# trailGuard.net
KiCad netlist of a schematic drawn in Altium Designer
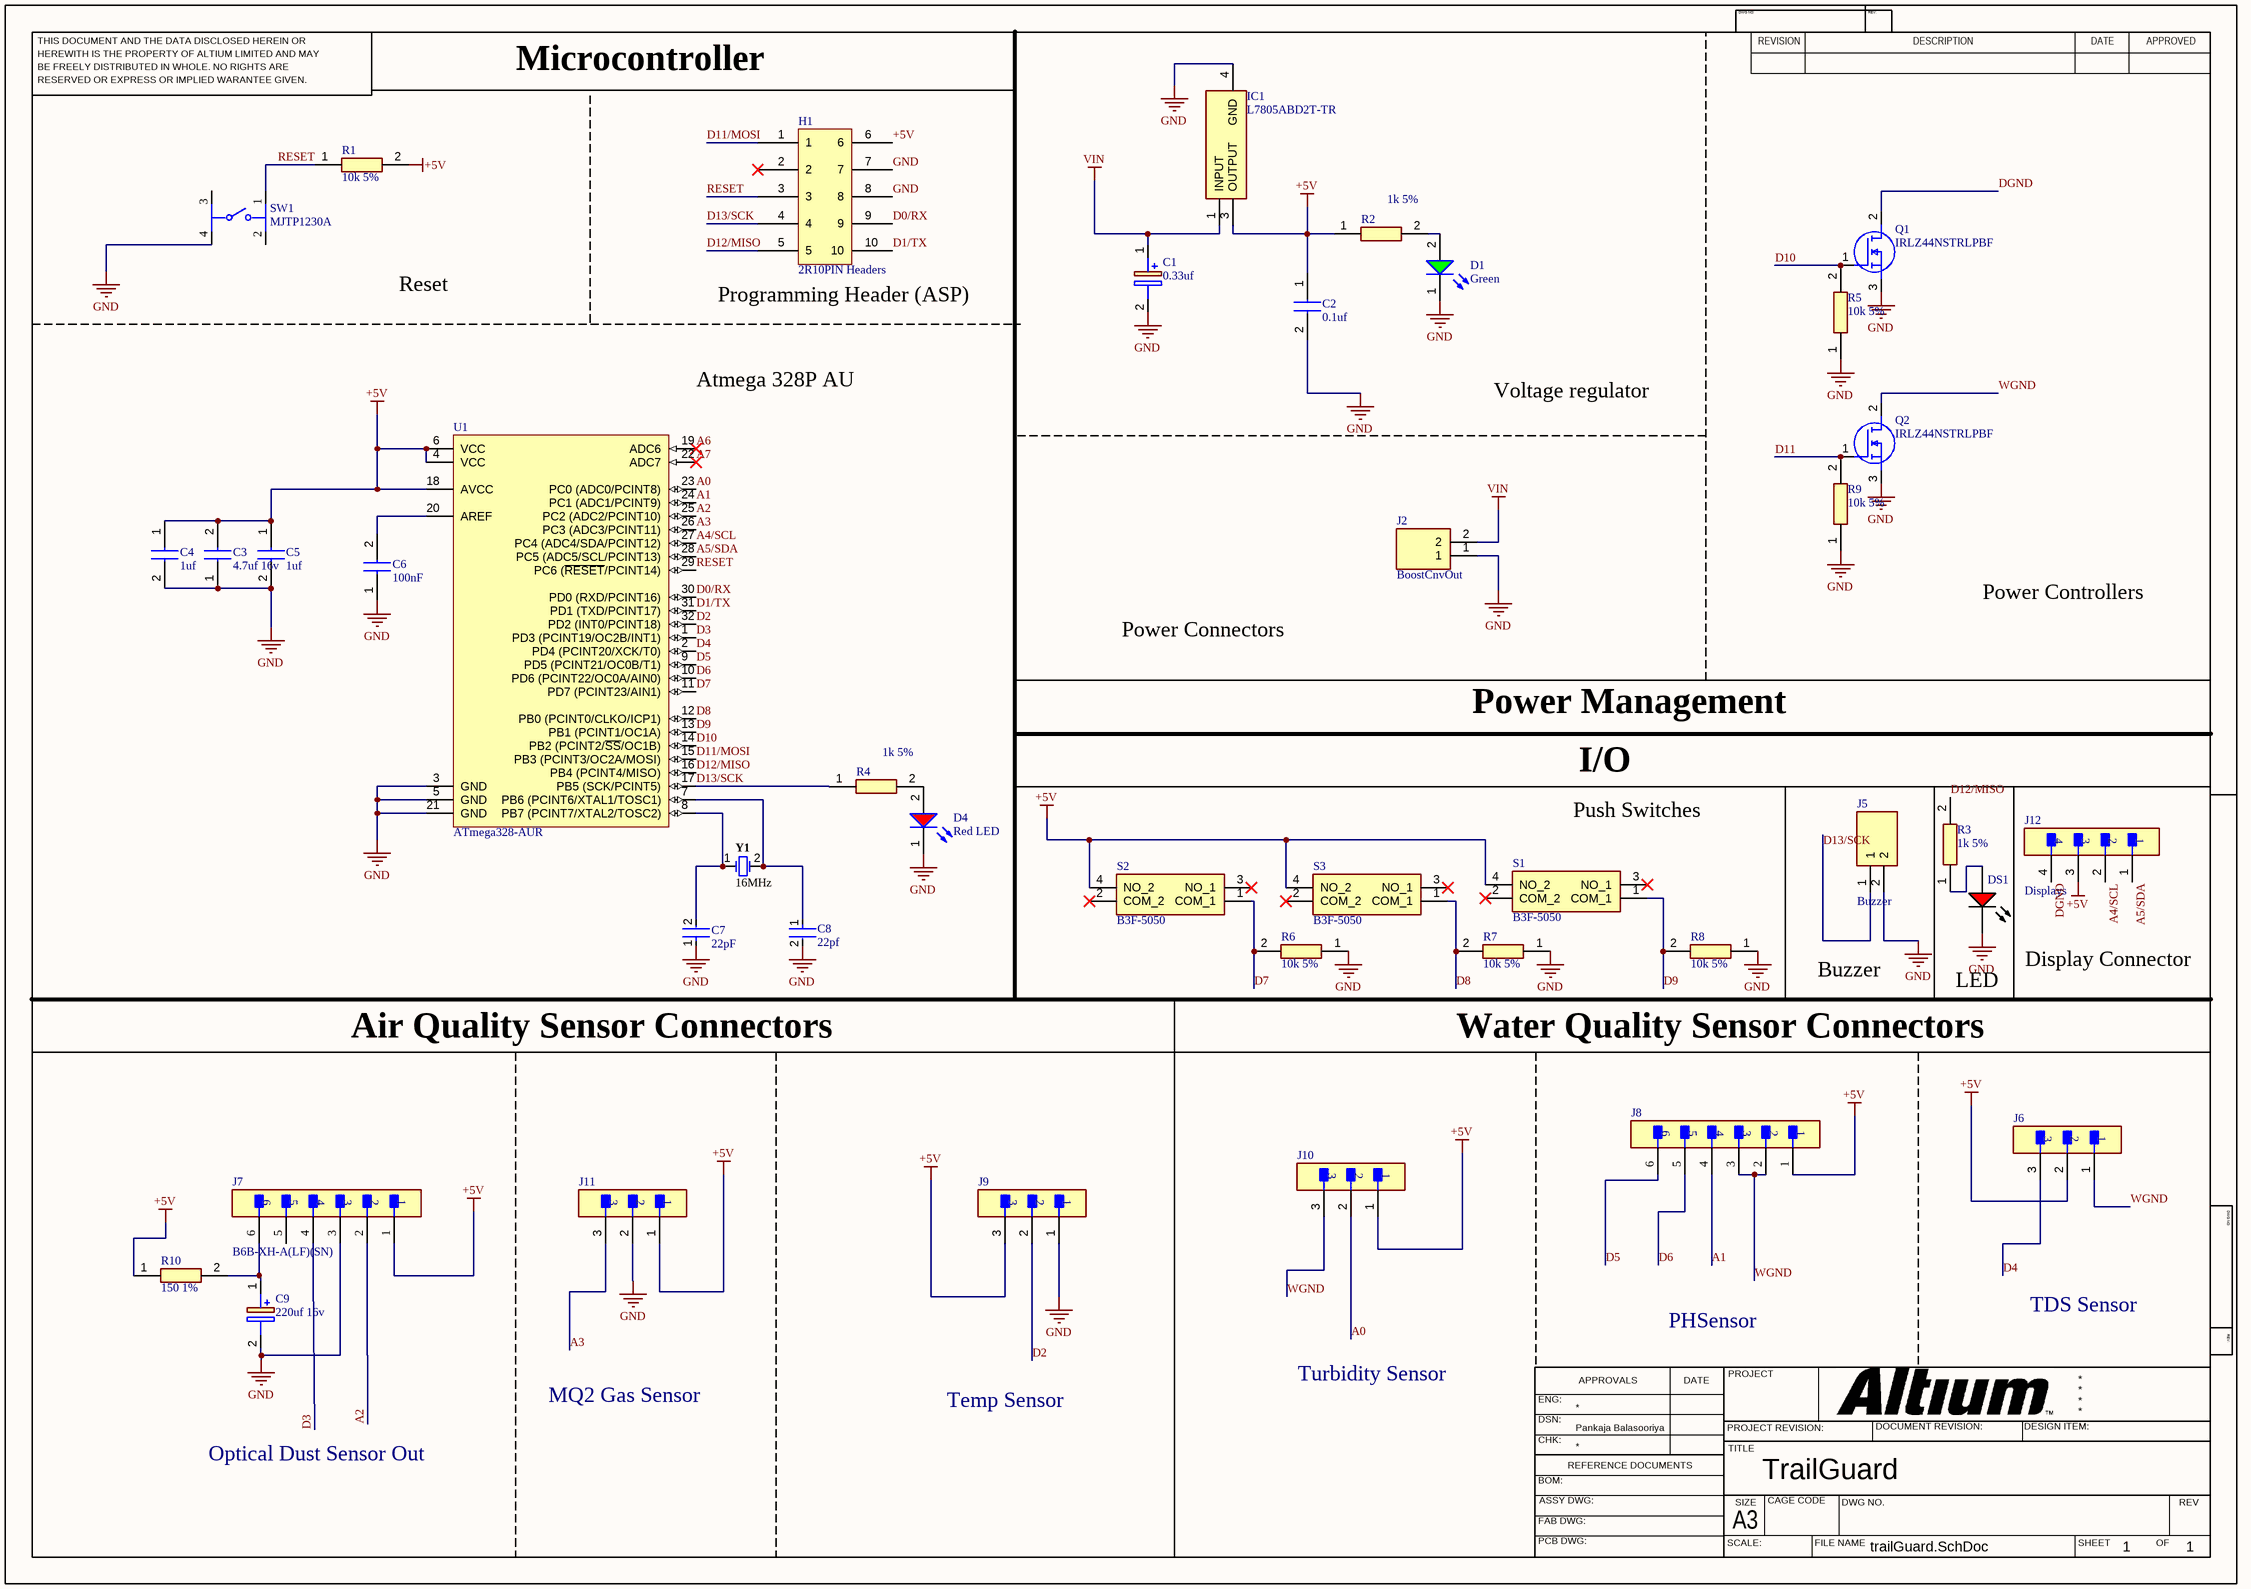
[diagram p0: trailGuard.SchDoc]

(export (version "E")
  (design (tool "Eeschema 10.0.6"))
  (components
    (comp (ref "C1")
      (value "0.33uf")
      (footprint "SamacSys:CAPPM3216X180N")
      (description "Capacitor Polarised")
      (fields
        (field (name "MANUFACTURER_PART_NUMBER") "293D334X9035A2TE3")
        (field (name "MOUSER PART NUMBER") "74-293D334X9035A2TE3")
      )
      (libsource (lib "*") (part "293D334X9035A2TE3"))
    )
    (comp (ref "C2")
      (value "0.1uf")
      (footprint "SamacSys:C1206")
      (description "Capacitor")
      (fields
        (field (name "MANUFACTURER_PART_NUMBER") "C1206C105K5RECTU")
        (field (name "MOUSER PART NUMBER") "80-C1206C105K5RECTU")
      )
      (libsource (lib "*") (part "C1206C105K5RECTU"))
    )
    (comp (ref "C3")
      (value "4.7uf 16v")
      (footprint "SamacSys:CAPC3216X180N")
      (description "Capacitor")
      (fields
        (field (name "MANUFACTURER_PART_NUMBER") "EMK316B7475KL-T")
        (field (name "MOUSER PART NUMBER") "963-EMK316B7475KL-T")
      )
      (libsource (lib "*") (part "EMK316B7475KL-T"))
    )
    (comp (ref "C4")
      (value "1uf")
      (footprint "SamacSys:C1206")
      (description "Capacitor")
      (fields
        (field (name "MANUFACTURER_PART_NUMBER") "C1206C105K5RECTU")
        (field (name "MOUSER PART NUMBER") "80-C1206C105K5RECTU")
      )
      (libsource (lib "*") (part "C1206C105K5RECTU"))
    )
    (comp (ref "C5")
      (value "1uf")
      (footprint "SamacSys:C1206")
      (description "Capacitor")
      (fields
        (field (name "MANUFACTURER_PART_NUMBER") "C1206C105K5RECTU")
        (field (name "MOUSER PART NUMBER") "80-C1206C105K5RECTU")
      )
      (libsource (lib "*") (part "C1206C105K5RECTU"))
    )
    (comp (ref "C6")
      (value "100nF")
      (footprint "SamacSys:CAPC3216X190N")
      (description "Capacitor")
      (fields
        (field (name "MANUFACTURER_PART_NUMBER") "MCJCU31LBB7104KTPA01")
        (field (name "MOUSER PART NUMBER") "963-MCJCU31LBB7104KT")
      )
      (libsource (lib "*") (part "MCJCU31LBB7104KTPA01"))
    )
    (comp (ref "C7")
      (value "22pF")
      (footprint "FP-CL21-IPC_C")
      (description "CL21 Series 0805 22pF 50V ±5% Tolerance C0G Multilayer Ceramic Chip Capacitor")
      (fields (field (name "TOLERANCE") "5%"))
      (libsource (lib "Altium Content Vault") (part "b4654b650e69147ec39a6b967a45e02"))
    )
    (comp (ref "C8")
      (value "22pf")
      (footprint "FP-CL21-IPC_C")
      (description "CL21 Series 0805 22pF 50V ±5% Tolerance C0G Multilayer Ceramic Chip Capacitor")
      (fields (field (name "TOLERANCE") "5%"))
      (libsource (lib "Altium Content Vault") (part "b4654b650e69147ec39a6b967a45e02"))
    )
    (comp (ref "C9")
      (value "220uf 16v")
      (footprint "SamacSys:EEE0JA331XP")
      (description "Capacitor Polarised")
      (fields
        (field (name "MANUFACTURER_PART_NUMBER") "EEE-FTE221XAP")
        (field (name "MOUSER PART NUMBER") "667-EEE-FTE221XAP")
      )
      (libsource (lib "*") (part "EEE-FTE221XAP"))
    )
    (comp (ref "D1")
      (value "Green")
      (footprint "WL-SMCW_0805_150080xx75000")
      (libsource (lib "Altium Content Vault") (part "LED_Green_2A-1K"))
    )
    (comp (ref "D4")
      (value "Red LED")
      (footprint "WL-SMCW_0805_150080xx75000")
      (libsource (lib "Altium Content Vault") (part "LED_Red_2A-1K"))
    )
    (comp (ref "DS1")
      (value "HLMP-3301")
      (footprint "AVAG-HLMP-3301-2")
      (description "T-1 3/4 (5 mm) Diffused LED Lamp, 1.9 V, -40 to 100 degC, 2-Pin THD, RoHS, Bulk")
      (fields (field (name "MANUFACTURER") "Avago"))
      (libsource (lib "Altium Content Vault") (part "LED-RED-K1A2-2"))
    )
    (comp (ref "H1")
      (value "2R10PIN Headers")
      (footprint "2R10PIN Headers")
      (libsource (lib "trailGuard") (part "2R10PIN Headers"))
    )
    (comp (ref "IC1")
      (value "L7805ABD2T-TR")
      (footprint "SamacSys:D2PAK-STB35NF10T4")
      (description "Integrated Circuit")
      (fields (field (name "MOUSER PART NUMBER") "511-L7805ABD2T-TR"))
      (libsource (lib "*") (part "L7805ABD2T-TR"))
    )
    (comp (ref "J2")
      (value "BoostCnvOut")
      (footprint "SamacSys:B2BXHAMLFSN")
      (description "Connector")
      (fields (field (name "MANUFACTURER_PART_NUMBER") "B2B-XH-AM(LF)(SN)"))
      (libsource (lib "*") (part "B2B-XH-AM_LF__SN_"))
    )
    (comp (ref "J5")
      (value "Buzzer")
      (footprint "SamacSys:B2BXHAMLFSN")
      (description "Connector")
      (fields (field (name "MANUFACTURER_PART_NUMBER") "B2B-XH-AM(LF)(SN)"))
      (libsource (lib "") (part "B2B-XH-AM_LF__SN__1"))
    )
    (comp (ref "J6")
      (value "B3B-XH-A(LF)(SN)")
      (footprint "FP-B3B-XH-A_LF_SN-MFG")
      (description "CONN HEADER VERT 3POS 2.5MM")
      (libsource (lib "Altium Content Vault") (part "0d3f023dd272f625e17a2be33dea85f"))
    )
    (comp (ref "J7")
      (value "B6B-XH-A(LF)(SN)")
      (footprint "FP-B6B-XH-A_LF_SN-MFG")
      (description "CONN HEADER VERT 6POS 2.5MM")
      (libsource (lib "Altium Content Vault") (part "f2cb566baf1c37ab5a3b8e90bbeafd6"))
    )
    (comp (ref "J8")
      (value "B6B-XH-A(LF)(SN)")
      (footprint "FP-B6B-XH-A_LF_SN-MFG")
      (description "CONN HEADER VERT 6POS 2.5MM")
      (libsource (lib "Altium Content Vault") (part "f2cb566baf1c37ab5a3b8e90bbeafd6"))
    )
    (comp (ref "J9")
      (value "B3B-XH-A(LF)(SN)")
      (footprint "FP-B3B-XH-A_LF_SN-MFG")
      (description "CONN HEADER VERT 3POS 2.5MM")
      (libsource (lib "Altium Content Vault") (part "0d3f023dd272f625e17a2be33dea85f"))
    )
    (comp (ref "J10")
      (value "B3B-XH-A(LF)(SN)")
      (footprint "FP-B3B-XH-A_LF_SN-MFG")
      (description "CONN HEADER VERT 3POS 2.5MM")
      (libsource (lib "Altium Content Vault") (part "0d3f023dd272f625e17a2be33dea85f"))
    )
    (comp (ref "J11")
      (value "B3B-XH-A(LF)(SN)")
      (footprint "FP-B3B-XH-A_LF_SN-MFG")
      (description "CONN HEADER VERT 3POS 2.5MM")
      (libsource (lib "Altium Content Vault") (part "0d3f023dd272f625e17a2be33dea85f"))
    )
    (comp (ref "J12")
      (value "Displays")
      (footprint "FP-B4B-XH-AM_LF_SN-MFG")
      (description "CONN HEADER VERT 4POS 2.5MM")
      (libsource (lib "Altium Content Vault") (part "299a8cea1bdcbc3624fe62c390fa72c"))
    )
    (comp (ref "Q1")
      (value "IRLZ44NSTRLPBF")
      (footprint "SamacSys:IRF2804STRLPBF")
      (description "MOSFET (N-Channel)")
      (fields (field (name "MOUSER PART NUMBER") "942-IRLZ44NSTRLPBF"))
      (libsource (lib "*") (part "IRLZ44NSTRLPBF"))
    )
    (comp (ref "Q2")
      (value "IRLZ44NSTRLPBF")
      (footprint "SamacSys:IRF2804STRLPBF")
      (description "MOSFET (N-Channel)")
      (fields (field (name "MOUSER PART NUMBER") "942-IRLZ44NSTRLPBF"))
      (libsource (lib "*") (part "IRLZ44NSTRLPBF"))
    )
    (comp (ref "R1")
      (value "10k 5%")
      (footprint "SamacSys:RESC3116X70N")
      (description "Resistor")
      (fields
        (field (name "MANUFACTURER_PART_NUMBER") "ERJ-8GEYJ103V")
        (field (name "MOUSER PART NUMBER") "667-ERJ-8GEYJ103V")
      )
      (libsource (lib "SamacSys") (part "ERJ-8GEYJ103V"))
    )
    (comp (ref "R2")
      (value "1k 5%")
      (footprint "SamacSys:RESC3116X70N")
      (description "Resistor")
      (fields
        (field (name "MANUFACTURER_PART_NUMBER") "ERJ-T08J102V")
        (field (name "MOUSER PART NUMBER") "667-ERJ-T08J102V")
      )
      (libsource (lib "*") (part "ERJ-T08J102V"))
    )
    (comp (ref "R3")
      (value "1k 5%")
      (footprint "SamacSys:RESC3116X70N")
      (description "Resistor")
      (fields
        (field (name "MANUFACTURER_PART_NUMBER") "ERJ-T08J102V")
        (field (name "MOUSER PART NUMBER") "667-ERJ-T08J102V")
      )
      (libsource (lib "") (part "ERJ-T08J102V_1"))
    )
    (comp (ref "R4")
      (value "1k 5%")
      (footprint "SamacSys:RESC3116X70N")
      (description "Resistor")
      (fields
        (field (name "MANUFACTURER_PART_NUMBER") "ERJ-T08J102V")
        (field (name "MOUSER PART NUMBER") "667-ERJ-T08J102V")
      )
      (libsource (lib "*") (part "ERJ-T08J102V"))
    )
    (comp (ref "R5")
      (value "10k 5%")
      (footprint "SamacSys:RESC3116X70N")
      (description "Resistor")
      (fields
        (field (name "MANUFACTURER_PART_NUMBER") "ERJ-8GEYJ103V")
        (field (name "MOUSER PART NUMBER") "667-ERJ-8GEYJ103V")
      )
      (libsource (lib "") (part "ERJ-8GEYJ103V_1"))
    )
    (comp (ref "R6")
      (value "10k 5%")
      (footprint "SamacSys:RESC3116X70N")
      (description "Resistor")
      (fields
        (field (name "MANUFACTURER_PART_NUMBER") "ERJ-8GEYJ103V")
        (field (name "MOUSER PART NUMBER") "667-ERJ-8GEYJ103V")
      )
      (libsource (lib "*") (part "ERJ-8GEYJ103V"))
    )
    (comp (ref "R7")
      (value "10k 5%")
      (footprint "SamacSys:RESC3116X70N")
      (description "Resistor")
      (fields
        (field (name "MANUFACTURER_PART_NUMBER") "ERJ-8GEYJ103V")
        (field (name "MOUSER PART NUMBER") "667-ERJ-8GEYJ103V")
      )
      (libsource (lib "*") (part "ERJ-8GEYJ103V"))
    )
    (comp (ref "R8")
      (value "10k 5%")
      (footprint "SamacSys:RESC3116X70N")
      (description "Resistor")
      (fields
        (field (name "MANUFACTURER_PART_NUMBER") "ERJ-8GEYJ103V")
        (field (name "MOUSER PART NUMBER") "667-ERJ-8GEYJ103V")
      )
      (libsource (lib "*") (part "ERJ-8GEYJ103V"))
    )
    (comp (ref "R9")
      (value "10k 5%")
      (footprint "SamacSys:RESC3116X70N")
      (description "Resistor")
      (fields
        (field (name "MANUFACTURER_PART_NUMBER") "ERJ-8GEYJ103V")
        (field (name "MOUSER PART NUMBER") "667-ERJ-8GEYJ103V")
      )
      (libsource (lib "") (part "ERJ-8GEYJ103V_1"))
    )
    (comp (ref "R10")
      (value "150 1%")
      (footprint "SamacSys:ERJ8ENF1000V")
      (description "Resistor")
      (fields
        (field (name "MANUFACTURER_PART_NUMBER") "ERJ-8ENF1500V")
        (field (name "MOUSER PART NUMBER") "667-ERJ-8ENF1500V")
      )
      (libsource (lib "*") (part "ERJ-8ENF1500V"))
    )
    (comp (ref "S1")
      (value "B3F-5050")
      (footprint "SamacSys:B3F-4055")
      (description "Switch")
      (fields (field (name "MOUSER PART NUMBER") "653-B3F-5050"))
      (libsource (lib "*") (part "B3F-5050"))
    )
    (comp (ref "S2")
      (value "B3F-5050")
      (footprint "SamacSys:B3F-4055")
      (description "Switch")
      (fields (field (name "MOUSER PART NUMBER") "653-B3F-5050"))
      (libsource (lib "*") (part "B3F-5050"))
    )
    (comp (ref "S3")
      (value "B3F-5050")
      (footprint "SamacSys:B3F-4055")
      (description "Switch")
      (fields (field (name "MOUSER PART NUMBER") "653-B3F-5050"))
      (libsource (lib "*") (part "B3F-5050"))
    )
    (comp (ref "SW1")
      (value "MJTP1230A")
      (footprint "FP-MJTP1230A-MFG")
      (description "SWITCH TACTILE SPST-NO 0.05A 12V")
      (libsource (lib "Altium Content Vault") (part "1adf0dd01260c80cf25a44bfd6b99ba"))
    )
    (comp (ref "U1")
      (value "ATmega328-AUR")
      (footprint "32A_L")
      (libsource (lib "Altium Content Vault") (part "MC-8B-ATM48-SQ32"))
    )
    (comp (ref "Y1")
      (value "16MHz")
      (footprint "FOX-FOXSLF160-20")
      (description "Resistance Weld Thru-Hole Crystal, 16 MHz, -20 to 70 degC, 2-Pin THD, RoHS, Bulk")
      (fields (field (name "TOLERANCE") "1%"))
      (libsource (lib "Altium Content Vault") (part "XTAL-1-2-2"))
    )
  )
  (nets
    (net (code "1") (name "+5V") (class "Default")
      (node (ref "C2") (pin "1") (pinfunction "1_1") (pintype "passive"))
      (node (ref "C3") (pin "2") (pinfunction "2_2") (pintype "passive"))
      (node (ref "C4") (pin "1") (pinfunction "1_1") (pintype "passive"))
      (node (ref "C5") (pin "1") (pinfunction "1_1") (pintype "passive"))
      (node (ref "H1") (pin "6") (pinfunction "6_6") (pintype "passive"))
      (node (ref "IC1") (pin "3") (pinfunction "OUTPUT_3") (pintype "passive"))
      (node (ref "J10") (pin "1") (pinfunction "1_1") (pintype "passive"))
      (node (ref "J11") (pin "1") (pinfunction "1_1") (pintype "passive"))
      (node (ref "J12") (pin "3") (pinfunction "3_3") (pintype "passive"))
      (node (ref "J6") (pin "2") (pinfunction "2_2") (pintype "passive"))
      (node (ref "J7") (pin "1") (pinfunction "1_1") (pintype "passive"))
      (node (ref "J8") (pin "1") (pinfunction "1_1") (pintype "passive"))
      (node (ref "J9") (pin "3") (pinfunction "3_3") (pintype "passive"))
      (node (ref "R1") (pin "2") (pinfunction "2_2") (pintype "passive"))
      (node (ref "R10") (pin "1") (pinfunction "1_1") (pintype "passive"))
      (node (ref "R2") (pin "1") (pinfunction "1_1") (pintype "passive"))
      (node (ref "S1") (pin "4") (pinfunction "NO_2_4") (pintype "passive"))
      (node (ref "S2") (pin "4") (pinfunction "NO_2_4") (pintype "passive"))
      (node (ref "S3") (pin "4") (pinfunction "NO_2_4") (pintype "passive"))
      (node (ref "U1") (pin "18") (pinfunction "AVCC_18") (pintype "power_in"))
      (node (ref "U1") (pin "4") (pinfunction "VCC_4") (pintype "power_in"))
      (node (ref "U1") (pin "6") (pinfunction "VCC_6") (pintype "power_in"))
    )
    (net (code "2") (name "/A0") (class "Default")
      (node (ref "J10") (pin "2") (pinfunction "2_2") (pintype "passive"))
      (node (ref "U1") (pin "23") (pinfunction "PC0_(ADC0/PCINT8)_23") (pintype "bidirectional"))
    )
    (net (code "3") (name "/A1") (class "Default")
      (node (ref "J8") (pin "4") (pinfunction "4_4") (pintype "passive"))
      (node (ref "U1") (pin "24") (pinfunction "PC1_(ADC1/PCINT9)_24") (pintype "bidirectional"))
    )
    (net (code "4") (name "/A2") (class "Default")
      (node (ref "J7") (pin "2") (pinfunction "2_2") (pintype "passive"))
      (node (ref "U1") (pin "25") (pinfunction "PC2_(ADC2/PCINT10)_25") (pintype "bidirectional"))
    )
    (net (code "5") (name "/A3") (class "Default")
      (node (ref "J11") (pin "3") (pinfunction "3_3") (pintype "passive"))
      (node (ref "U1") (pin "26") (pinfunction "PC3_(ADC3/PCINT11)_26") (pintype "bidirectional"))
    )
    (net (code "6") (name "/A4{slash}SCL") (class "Default")
      (node (ref "J12") (pin "2") (pinfunction "2_2") (pintype "passive"))
      (node (ref "U1") (pin "27") (pinfunction "PC4_(ADC4/SDA/PCINT12)_27") (pintype "bidirectional"))
    )
    (net (code "7") (name "/A5{slash}SDA") (class "Default")
      (node (ref "J12") (pin "1") (pinfunction "1_1") (pintype "passive"))
      (node (ref "U1") (pin "28") (pinfunction "PC5_(ADC5/SCL/PCINT13)_28") (pintype "bidirectional"))
    )
    (net (code "8") (name "/A6") (class "Default")
      (node (ref "U1") (pin "19") (pinfunction "ADC6_19") (pintype "input+no_connect"))
    )
    (net (code "9") (name "/A7") (class "Default")
      (node (ref "U1") (pin "22") (pinfunction "ADC7_22") (pintype "input+no_connect"))
    )
    (net (code "10") (name "/D0{slash}RX") (class "Default")
      (node (ref "H1") (pin "9") (pinfunction "9_9") (pintype "passive"))
      (node (ref "U1") (pin "30") (pinfunction "PD0_(RXD/PCINT16)_30") (pintype "bidirectional"))
    )
    (net (code "11") (name "/D1{slash}TX") (class "Default")
      (node (ref "H1") (pin "10") (pinfunction "10_10") (pintype "passive"))
      (node (ref "U1") (pin "31") (pinfunction "PD1_(TXD/PCINT17)_31") (pintype "bidirectional"))
    )
    (net (code "12") (name "/D2") (class "Default")
      (node (ref "J9") (pin "2") (pinfunction "2_2") (pintype "passive"))
      (node (ref "U1") (pin "32") (pinfunction "PD2_(INT0/PCINT18)_32") (pintype "bidirectional"))
    )
    (net (code "13") (name "/D3") (class "Default")
      (node (ref "J7") (pin "4") (pinfunction "4_4") (pintype "passive"))
      (node (ref "U1") (pin "1") (pinfunction "PD3_(PCINT19/OC2B/INT1)_1") (pintype "bidirectional"))
    )
    (net (code "14") (name "/D4") (class "Default")
      (node (ref "J6") (pin "3") (pinfunction "3_3") (pintype "passive"))
      (node (ref "U1") (pin "2") (pinfunction "PD4_(PCINT20/XCK/T0)_2") (pintype "bidirectional"))
    )
    (net (code "15") (name "/D5") (class "Default")
      (node (ref "J8") (pin "6") (pinfunction "6_6") (pintype "passive"))
      (node (ref "U1") (pin "9") (pinfunction "PD5_(PCINT21/OC0B/T1)_9") (pintype "bidirectional"))
    )
    (net (code "16") (name "/D6") (class "Default")
      (node (ref "J8") (pin "5") (pinfunction "5_5") (pintype "passive"))
      (node (ref "U1") (pin "10") (pinfunction "PD6_(PCINT22/OC0A/AIN0)_10") (pintype "bidirectional"))
    )
    (net (code "17") (name "/D7") (class "Default")
      (node (ref "R6") (pin "2") (pinfunction "2_2") (pintype "passive"))
      (node (ref "S2") (pin "1") (pinfunction "COM_1_1") (pintype "passive"))
      (node (ref "U1") (pin "11") (pinfunction "PD7_(PCINT23/AIN1)_11") (pintype "bidirectional"))
    )
    (net (code "18") (name "/D8") (class "Default")
      (node (ref "R7") (pin "2") (pinfunction "2_2") (pintype "passive"))
      (node (ref "S3") (pin "1") (pinfunction "COM_1_1") (pintype "passive"))
      (node (ref "U1") (pin "12") (pinfunction "PB0_(PCINT0/CLKO/ICP1)_12") (pintype "bidirectional"))
    )
    (net (code "19") (name "/D9") (class "Default")
      (node (ref "R8") (pin "2") (pinfunction "2_2") (pintype "passive"))
      (node (ref "S1") (pin "1") (pinfunction "COM_1_1") (pintype "passive"))
      (node (ref "U1") (pin "13") (pinfunction "PB1_(PCINT1/OC1A)_13") (pintype "bidirectional"))
    )
    (net (code "20") (name "/D10") (class "Default")
      (node (ref "Q1") (pin "1") (pinfunction "G_1") (pintype "passive"))
      (node (ref "R5") (pin "2") (pinfunction "2_2") (pintype "passive"))
      (node (ref "U1") (pin "14") (pinfunction "PB2_(PCINT2/~{SS}/OC1B)_14") (pintype "bidirectional"))
    )
    (net (code "21") (name "/D11") (class "Default")
      (node (ref "Q2") (pin "1") (pinfunction "G_1") (pintype "passive"))
      (node (ref "R9") (pin "2") (pinfunction "2_2") (pintype "passive"))
    )
    (net (code "22") (name "/D11{slash}MOSI") (class "Default")
      (node (ref "H1") (pin "1") (pinfunction "1_1") (pintype "passive"))
      (node (ref "U1") (pin "15") (pinfunction "PB3_(PCINT3/OC2A/MOSI)_15") (pintype "bidirectional"))
    )
    (net (code "23") (name "/D12{slash}MISO") (class "Default")
      (node (ref "H1") (pin "5") (pinfunction "5_5") (pintype "passive"))
      (node (ref "R3") (pin "2") (pinfunction "2_2") (pintype "passive"))
      (node (ref "U1") (pin "16") (pinfunction "PB4_(PCINT4/MISO)_16") (pintype "bidirectional"))
    )
    (net (code "24") (name "/D13{slash}SCK") (class "Default")
      (node (ref "H1") (pin "4") (pinfunction "4_4") (pintype "passive"))
      (node (ref "J5") (pin "1") (pinfunction "1_1") (pintype "passive"))
      (node (ref "R4") (pin "1") (pinfunction "1_1") (pintype "passive"))
      (node (ref "U1") (pin "17") (pinfunction "PB5_(SCK/PCINT5)_17") (pintype "bidirectional"))
    )
    (net (code "25") (name "/DGND") (class "Default")
      (node (ref "J12") (pin "4") (pinfunction "4_4") (pintype "passive"))
      (node (ref "Q1") (pin "2") (pinfunction "D_2") (pintype "passive"))
    )
    (net (code "26") (name "/RESET") (class "Default")
      (node (ref "H1") (pin "3") (pinfunction "3_3") (pintype "passive"))
      (node (ref "R1") (pin "1") (pinfunction "1_1") (pintype "passive"))
      (node (ref "SW1") (pin "1") (pinfunction "1_1") (pintype "passive"))
      (node (ref "U1") (pin "29") (pinfunction "PC6_(~{RESET}/PCINT14)_29") (pintype "bidirectional"))
    )
    (net (code "27") (name "/WGND") (class "Default")
      (node (ref "J10") (pin "3") (pinfunction "3_3") (pintype "passive"))
      (node (ref "J6") (pin "1") (pinfunction "1_1") (pintype "passive"))
      (node (ref "J8") (pin "2") (pinfunction "2_2") (pintype "passive"))
      (node (ref "J8") (pin "3") (pinfunction "3_3") (pintype "passive"))
      (node (ref "Q2") (pin "2") (pinfunction "D_2") (pintype "passive"))
    )
    (net (code "28") (name "GND") (class "Default")
      (node (ref "C1") (pin "2") (pinfunction "-_2") (pintype "passive"))
      (node (ref "C2") (pin "2") (pinfunction "2_2") (pintype "passive"))
      (node (ref "C3") (pin "1") (pinfunction "1_1") (pintype "passive"))
      (node (ref "C4") (pin "2") (pinfunction "2_2") (pintype "passive"))
      (node (ref "C5") (pin "2") (pinfunction "2_2") (pintype "passive"))
      (node (ref "C6") (pin "1") (pinfunction "1_1") (pintype "passive"))
      (node (ref "C7") (pin "1") (pinfunction "1_1") (pintype "passive"))
      (node (ref "C8") (pin "2") (pinfunction "2_2") (pintype "passive"))
      (node (ref "C9") (pin "2") (pinfunction "-_2") (pintype "passive"))
      (node (ref "D1") (pin "1") (pinfunction "K_1") (pintype "passive"))
      (node (ref "D4") (pin "1") (pinfunction "K_1") (pintype "passive"))
      (node (ref "DS1") (pin "1") (pinfunction "K_1") (pintype "passive"))
      (node (ref "H1") (pin "7") (pinfunction "7_7") (pintype "passive"))
      (node (ref "H1") (pin "8") (pinfunction "8_8") (pintype "passive"))
      (node (ref "IC1") (pin "4") (pinfunction "GND_4") (pintype "passive"))
      (node (ref "J11") (pin "2") (pinfunction "2_2") (pintype "passive"))
      (node (ref "J2") (pin "1") (pinfunction "1_1") (pintype "passive"))
      (node (ref "J5") (pin "2") (pinfunction "2_2") (pintype "passive"))
      (node (ref "J7") (pin "3") (pinfunction "3_3") (pintype "passive"))
      (node (ref "J9") (pin "1") (pinfunction "1_1") (pintype "passive"))
      (node (ref "Q1") (pin "3") (pinfunction "S_3") (pintype "passive"))
      (node (ref "Q2") (pin "3") (pinfunction "S_3") (pintype "passive"))
      (node (ref "R5") (pin "1") (pinfunction "1_1") (pintype "passive"))
      (node (ref "R6") (pin "1") (pinfunction "1_1") (pintype "passive"))
      (node (ref "R7") (pin "1") (pinfunction "1_1") (pintype "passive"))
      (node (ref "R8") (pin "1") (pinfunction "1_1") (pintype "passive"))
      (node (ref "R9") (pin "1") (pinfunction "1_1") (pintype "passive"))
      (node (ref "SW1") (pin "4") (pinfunction "4_4") (pintype "passive"))
      (node (ref "U1") (pin "21") (pinfunction "GND_21") (pintype "power_in"))
      (node (ref "U1") (pin "3") (pinfunction "GND_3") (pintype "power_in"))
      (node (ref "U1") (pin "5") (pinfunction "GND_5") (pintype "power_in"))
    )
    (net (code "29") (name "Net-(C9-+)") (class "Default")
      (node (ref "C9") (pin "1") (pinfunction "+_1") (pintype "passive"))
      (node (ref "J7") (pin "6") (pinfunction "6_6") (pintype "passive"))
      (node (ref "R10") (pin "2") (pinfunction "2_2") (pintype "passive"))
    )
    (net (code "30") (name "Net-(D1-A)") (class "Default")
      (node (ref "D1") (pin "2") (pinfunction "A_2") (pintype "passive"))
      (node (ref "R2") (pin "2") (pinfunction "2_2") (pintype "passive"))
    )
    (net (code "31") (name "Net-(D4-A)") (class "Default")
      (node (ref "D4") (pin "2") (pinfunction "A_2") (pintype "passive"))
      (node (ref "R4") (pin "2") (pinfunction "2_2") (pintype "passive"))
    )
    (net (code "32") (name "Net-(DS1-A)") (class "Default")
      (node (ref "DS1") (pin "2") (pinfunction "A_2") (pintype "passive"))
      (node (ref "R3") (pin "1") (pinfunction "1_1") (pintype "passive"))
    )
    (net (code "33") (name "Net-(U1-AREF)") (class "Default")
      (node (ref "C6") (pin "2") (pinfunction "2_2") (pintype "passive"))
      (node (ref "U1") (pin "20") (pinfunction "AREF_20") (pintype "passive"))
    )
    (net (code "34") (name "Net-(U1-PB6_(PCINT6{slash}XTAL1{slash}TOSC1))") (class "Default")
      (node (ref "C8") (pin "1") (pinfunction "1_1") (pintype "passive"))
      (node (ref "U1") (pin "7") (pinfunction "PB6_(PCINT6/XTAL1/TOSC1)_7") (pintype "bidirectional"))
      (node (ref "Y1") (pin "2") (pinfunction "2_2") (pintype "passive"))
    )
    (net (code "35") (name "Net-(U1-PB7_(PCINT7{slash}XTAL2{slash}TOSC2))") (class "Default")
      (node (ref "C7") (pin "2") (pinfunction "2_2") (pintype "passive"))
      (node (ref "U1") (pin "8") (pinfunction "PB7_(PCINT7/XTAL2/TOSC2)_8") (pintype "bidirectional"))
      (node (ref "Y1") (pin "1") (pinfunction "1_1") (pintype "passive"))
    )
    (net (code "36") (name "VIN") (class "Default")
      (node (ref "C1") (pin "1") (pinfunction "+_1") (pintype "passive"))
      (node (ref "IC1") (pin "1") (pinfunction "INPUT_1") (pintype "passive"))
      (node (ref "J2") (pin "2") (pinfunction "2_2") (pintype "passive"))
    )
    (net (code "37") (name "unconnected-(H1-Pad2)") (class "Default")
      (node (ref "H1") (pin "2") (pinfunction "2_2") (pintype "passive+no_connect"))
    )
    (net (code "38") (name "unconnected-(J7-Pad5)") (class "Default")
      (node (ref "J7") (pin "5") (pinfunction "5_5") (pintype "passive"))
    )
    (net (code "39") (name "unconnected-(S1-COM_2-Pad2)") (class "Default")
      (node (ref "S1") (pin "2") (pinfunction "COM_2_2") (pintype "passive+no_connect"))
    )
    (net (code "40") (name "unconnected-(S1-NO_1-Pad3)") (class "Default")
      (node (ref "S1") (pin "3") (pinfunction "NO_1_3") (pintype "passive+no_connect"))
    )
    (net (code "41") (name "unconnected-(S2-COM_2-Pad2)") (class "Default")
      (node (ref "S2") (pin "2") (pinfunction "COM_2_2") (pintype "passive+no_connect"))
    )
    (net (code "42") (name "unconnected-(S2-NO_1-Pad3)") (class "Default")
      (node (ref "S2") (pin "3") (pinfunction "NO_1_3") (pintype "passive+no_connect"))
    )
    (net (code "43") (name "unconnected-(S3-COM_2-Pad2)") (class "Default")
      (node (ref "S3") (pin "2") (pinfunction "COM_2_2") (pintype "passive+no_connect"))
    )
    (net (code "44") (name "unconnected-(S3-NO_1-Pad3)") (class "Default")
      (node (ref "S3") (pin "3") (pinfunction "NO_1_3") (pintype "passive+no_connect"))
    )
    (net (code "45") (name "unconnected-(SW1-Pad2)") (class "Default")
      (node (ref "SW1") (pin "2") (pinfunction "2_2") (pintype "passive"))
    )
    (net (code "46") (name "unconnected-(SW1-Pad3)") (class "Default")
      (node (ref "SW1") (pin "3") (pinfunction "3_3") (pintype "passive"))
    )
  )
)
